# flight_controller_with_pcb_frame.net
KiCad netlist of a schematic drawn in EAGLE
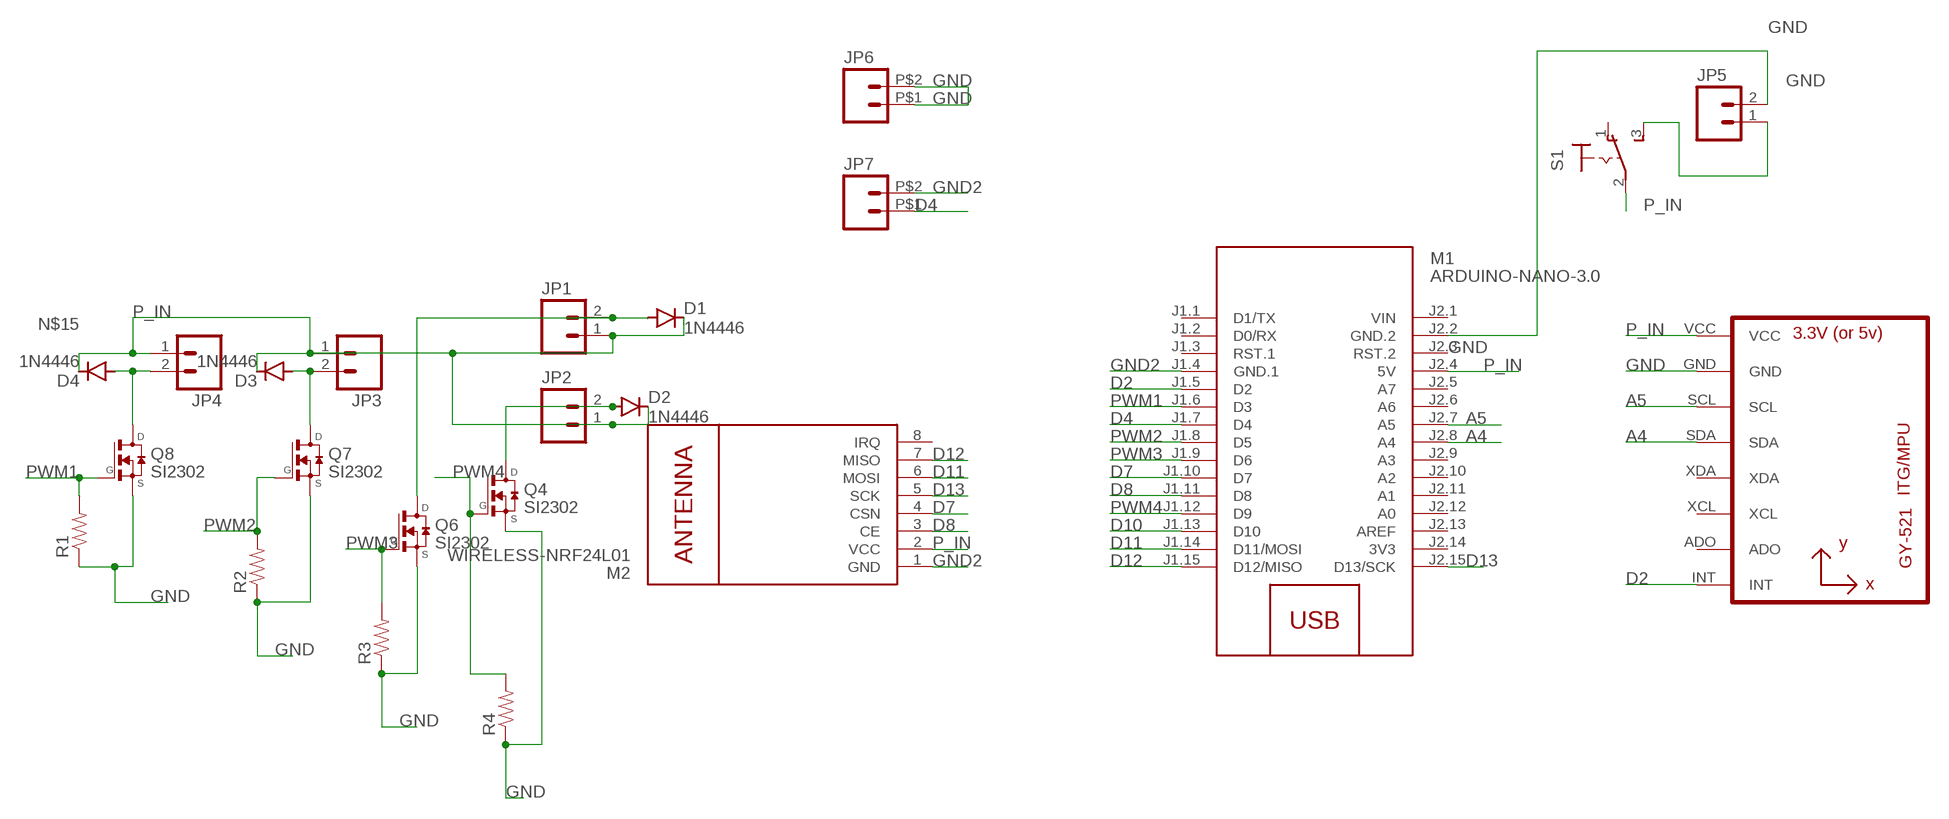
[diagram p0: schematic, sheet 1]

(export (version "E")
  (design (tool "Eeschema 10.0.6"))
  (components
    (comp (ref "D1")
      (value "1N4446")
      (footprint "eagle-import:DO35-10")
      (libsource (lib "eagle-import") (part "1N4446"))
    )
    (comp (ref "D2")
      (value "1N4446")
      (footprint "eagle-import:DO35-10")
      (libsource (lib "eagle-import") (part "1N4446"))
    )
    (comp (ref "D3")
      (value "1N4446")
      (footprint "eagle-import:DO35-10")
      (libsource (lib "eagle-import") (part "1N4446"))
    )
    (comp (ref "D4")
      (value "1N4446")
      (footprint "eagle-import:DO35-10")
      (libsource (lib "eagle-import") (part "1N4446"))
    )
    (comp (ref "JP1")
      (value "M021X02_NO_SILK")
      (footprint "eagle-import:1X02_NO_SILK")
      (libsource (lib "eagle-import") (part "M021X02_NO_SILK"))
    )
    (comp (ref "JP2")
      (value "M021X02_NO_SILK")
      (footprint "eagle-import:1X02_NO_SILK")
      (libsource (lib "eagle-import") (part "M021X02_NO_SILK"))
    )
    (comp (ref "JP3")
      (value "M021X02_NO_SILK")
      (footprint "eagle-import:1X02_NO_SILK")
      (libsource (lib "eagle-import") (part "M021X02_NO_SILK"))
    )
    (comp (ref "JP4")
      (value "M021X02_NO_SILK")
      (footprint "eagle-import:1X02_NO_SILK")
      (libsource (lib "eagle-import") (part "M021X02_NO_SILK"))
    )
    (comp (ref "JP5")
      (value "M02PTH")
      (footprint "eagle-import:1X02")
      (libsource (lib "eagle-import") (part "M02PTH"))
    )
    (comp (ref "JP6")
      (value "M02PTH2")
      (footprint "eagle-import:1X02_BIG")
      (libsource (lib "eagle-import") (part "M02PTH2"))
    )
    (comp (ref "JP7")
      (value "M02PTH2")
      (footprint "eagle-import:1X02_BIG")
      (libsource (lib "eagle-import") (part "M02PTH2"))
    )
    (comp (ref "M1")
      (value "ARDUINO-NANO-3.0")
      (footprint "eagle-import:ARDUINO-NANO-3.0")
      (libsource (lib "eagle-import") (part "ARDUINO-NANO-3.0"))
    )
    (comp (ref "M2")
      (value "WIRELESS-NRF24L01")
      (footprint "eagle-import:WIRELESS-NRF24L01")
      (libsource (lib "eagle-import") (part "WIRELESS-NRF24L01"))
    )
    (comp (ref "Q4")
      (value "SI2302")
      (footprint "eagle-import:SOT23")
      (libsource (lib "eagle-import") (part "SI2302"))
    )
    (comp (ref "Q6")
      (value "SI2302")
      (footprint "eagle-import:SOT23")
      (libsource (lib "eagle-import") (part "SI2302"))
    )
    (comp (ref "Q7")
      (value "SI2302")
      (footprint "eagle-import:SOT23")
      (libsource (lib "eagle-import") (part "SI2302"))
    )
    (comp (ref "Q8")
      (value "SI2302")
      (footprint "eagle-import:SOT23")
      (libsource (lib "eagle-import") (part "SI2302"))
    )
    (comp (ref "R1")
      (value "RESISTORAXIAL-0.3")
      (footprint "eagle-import:AXIAL-0.3")
      (libsource (lib "eagle-import") (part "RESISTORAXIAL-0.3"))
    )
    (comp (ref "R2")
      (value "RESISTORAXIAL-0.3")
      (footprint "eagle-import:AXIAL-0.3")
      (libsource (lib "eagle-import") (part "RESISTORAXIAL-0.3"))
    )
    (comp (ref "R3")
      (value "RESISTORAXIAL-0.3")
      (footprint "eagle-import:AXIAL-0.3")
      (libsource (lib "eagle-import") (part "RESISTORAXIAL-0.3"))
    )
    (comp (ref "R4")
      (value "RESISTORAXIAL-0.3")
      (footprint "eagle-import:AXIAL-0.3")
      (libsource (lib "eagle-import") (part "RESISTORAXIAL-0.3"))
    )
    (comp (ref "S1")
      (value "M9040P")
      (footprint "eagle-import:M9040P")
      (libsource (lib "eagle-import") (part "M9040P"))
    )
    (comp (ref "U1")
      (value "GY-521MPU6050")
      (footprint "eagle-import:GY-521")
      (libsource (lib "eagle-import") (part "GY-521MPU6050"))
    )
  )
  (nets
    (net (code "1") (name "/3V3") (class "Default")
      (node (ref "M1") (pin "J2.14") (pinfunction "3V3_J2.14") (pintype "power_in"))
    )
    (net (code "2") (name "/A4") (class "Default")
      (node (ref "M1") (pin "J2.8") (pinfunction "A4_J2.8") (pintype "bidirectional"))
      (node (ref "U1") (pin "SDA") (pinfunction "SDA_SDA") (pintype "bidirectional"))
    )
    (net (code "3") (name "/A5") (class "Default")
      (node (ref "M1") (pin "J2.7") (pinfunction "A5_J2.7") (pintype "bidirectional"))
      (node (ref "U1") (pin "SCL") (pinfunction "SCL_SCL") (pintype "bidirectional"))
    )
    (net (code "4") (name "/D2") (class "Default")
      (node (ref "M1") (pin "J1.5") (pinfunction "D2_J1.5") (pintype "bidirectional"))
      (node (ref "U1") (pin "INT") (pinfunction "INT_INT") (pintype "bidirectional"))
    )
    (net (code "5") (name "/D4") (class "Default")
      (node (ref "JP7") (pin "P$1") (pinfunction "1_P$1") (pintype "passive"))
      (node (ref "M1") (pin "J1.7") (pinfunction "D4_J1.7") (pintype "bidirectional"))
    )
    (net (code "6") (name "/D7") (class "Default")
      (node (ref "M1") (pin "J1.10") (pinfunction "D7_J1.10") (pintype "bidirectional"))
      (node (ref "M2") (pin "4") (pinfunction "CSN_4") (pintype "bidirectional"))
    )
    (net (code "7") (name "/D8") (class "Default")
      (node (ref "M1") (pin "J1.11") (pinfunction "D8_J1.11") (pintype "bidirectional"))
      (node (ref "M2") (pin "3") (pinfunction "CE_3") (pintype "bidirectional"))
    )
    (net (code "8") (name "/D10") (class "Default")
      (node (ref "M1") (pin "J1.13") (pinfunction "D10_J1.13") (pintype "bidirectional"))
    )
    (net (code "9") (name "/D11") (class "Default")
      (node (ref "M1") (pin "J1.14") (pinfunction "D11/MOSI_J1.14") (pintype "bidirectional"))
      (node (ref "M2") (pin "6") (pinfunction "MOSI_6") (pintype "bidirectional"))
    )
    (net (code "10") (name "/D12") (class "Default")
      (node (ref "M1") (pin "J1.15") (pinfunction "D12/MISO_J1.15") (pintype "bidirectional"))
      (node (ref "M2") (pin "7") (pinfunction "MISO_7") (pintype "bidirectional"))
    )
    (net (code "11") (name "/D13") (class "Default")
      (node (ref "M1") (pin "J2.15") (pinfunction "D13/SCK_J2.15") (pintype "bidirectional"))
      (node (ref "M2") (pin "5") (pinfunction "SCK_5") (pintype "bidirectional"))
    )
    (net (code "12") (name "/GND") (class "Default")
      (node (ref "JP5") (pin "2") (pinfunction "2_2") (pintype "passive"))
      (node (ref "JP6") (pin "P$1") (pinfunction "1_P$1") (pintype "passive"))
      (node (ref "JP6") (pin "P$2") (pinfunction "2_P$2") (pintype "passive"))
      (node (ref "M1") (pin "J2.2") (pinfunction "GND.2_J2.2") (pintype "power_in"))
      (node (ref "Q4") (pin "2") (pinfunction "S_2") (pintype "passive"))
      (node (ref "Q6") (pin "2") (pinfunction "S_2") (pintype "passive"))
      (node (ref "Q7") (pin "2") (pinfunction "S_2") (pintype "passive"))
      (node (ref "Q8") (pin "2") (pinfunction "S_2") (pintype "passive"))
      (node (ref "R1") (pin "P$1") (pinfunction "1_P$1") (pintype "passive"))
      (node (ref "R2") (pin "P$1") (pinfunction "1_P$1") (pintype "passive"))
      (node (ref "R3") (pin "P$1") (pinfunction "1_P$1") (pintype "passive"))
      (node (ref "R4") (pin "P$1") (pinfunction "1_P$1") (pintype "passive"))
      (node (ref "U1") (pin "GND") (pinfunction "GND_GND") (pintype "bidirectional"))
    )
    (net (code "13") (name "/GND2") (class "Default")
      (node (ref "JP7") (pin "P$2") (pinfunction "2_P$2") (pintype "passive"))
      (node (ref "M1") (pin "J1.4") (pinfunction "GND.1_J1.4") (pintype "power_in"))
      (node (ref "M2") (pin "1") (pinfunction "GND_1") (pintype "power_in"))
    )
    (net (code "14") (name "/N$15") (class "Default")
      (node (ref "D4") (pin "A") (pinfunction "A_A") (pintype "passive"))
      (node (ref "JP4") (pin "2") (pinfunction "2_2") (pintype "passive"))
      (node (ref "Q8") (pin "3") (pinfunction "D_3") (pintype "passive"))
    )
    (net (code "15") (name "/PWM1") (class "Default")
      (node (ref "M1") (pin "J1.6") (pinfunction "D3_J1.6") (pintype "bidirectional"))
      (node (ref "Q8") (pin "1") (pinfunction "G_1") (pintype "passive"))
      (node (ref "R1") (pin "P$2") (pinfunction "2_P$2") (pintype "passive"))
    )
    (net (code "16") (name "/PWM2") (class "Default")
      (node (ref "M1") (pin "J1.8") (pinfunction "D5_J1.8") (pintype "bidirectional"))
      (node (ref "Q7") (pin "1") (pinfunction "G_1") (pintype "passive"))
      (node (ref "R2") (pin "P$2") (pinfunction "2_P$2") (pintype "passive"))
    )
    (net (code "17") (name "/PWM3") (class "Default")
      (node (ref "M1") (pin "J1.9") (pinfunction "D6_J1.9") (pintype "bidirectional"))
      (node (ref "Q6") (pin "1") (pinfunction "G_1") (pintype "passive"))
      (node (ref "R3") (pin "P$2") (pinfunction "2_P$2") (pintype "passive"))
    )
    (net (code "18") (name "/PWM4") (class "Default")
      (node (ref "M1") (pin "J1.12") (pinfunction "D9_J1.12") (pintype "bidirectional"))
      (node (ref "Q4") (pin "1") (pinfunction "G_1") (pintype "passive"))
      (node (ref "R4") (pin "P$2") (pinfunction "2_P$2") (pintype "passive"))
    )
    (net (code "19") (name "/P_IN") (class "Default")
      (node (ref "D1") (pin "C") (pinfunction "C_C") (pintype "passive"))
      (node (ref "D2") (pin "C") (pinfunction "C_C") (pintype "passive"))
      (node (ref "D3") (pin "C") (pinfunction "C_C") (pintype "passive"))
      (node (ref "D4") (pin "C") (pinfunction "C_C") (pintype "passive"))
      (node (ref "JP1") (pin "1") (pinfunction "1_1") (pintype "passive"))
      (node (ref "JP2") (pin "1") (pinfunction "1_1") (pintype "passive"))
      (node (ref "JP3") (pin "1") (pinfunction "1_1") (pintype "passive"))
      (node (ref "JP4") (pin "1") (pinfunction "1_1") (pintype "passive"))
      (node (ref "M1") (pin "J2.4") (pinfunction "5V_J2.4") (pintype "power_in"))
      (node (ref "M2") (pin "2") (pinfunction "VCC_2") (pintype "power_in"))
      (node (ref "S1") (pin "2") (pinfunction "P_2") (pintype "passive"))
      (node (ref "U1") (pin "VCC") (pinfunction "VCC_VCC") (pintype "bidirectional"))
    )
    (net (code "20") (name "/VIN") (class "Default")
      (node (ref "M1") (pin "J2.1") (pinfunction "VIN_J2.1") (pintype "power_in"))
    )
    (net (code "21") (name "Net-(Q4-D)") (class "Default")
      (node (ref "D2") (pin "A") (pinfunction "A_A") (pintype "passive"))
      (node (ref "JP2") (pin "2") (pinfunction "2_2") (pintype "passive"))
      (node (ref "Q4") (pin "3") (pinfunction "D_3") (pintype "passive"))
    )
    (net (code "22") (name "Net-(Q6-D)") (class "Default")
      (node (ref "D1") (pin "A") (pinfunction "A_A") (pintype "passive"))
      (node (ref "JP1") (pin "2") (pinfunction "2_2") (pintype "passive"))
      (node (ref "Q6") (pin "3") (pinfunction "D_3") (pintype "passive"))
    )
    (net (code "23") (name "Net-(Q7-D)") (class "Default")
      (node (ref "D3") (pin "A") (pinfunction "A_A") (pintype "passive"))
      (node (ref "JP3") (pin "2") (pinfunction "2_2") (pintype "passive"))
      (node (ref "Q7") (pin "3") (pinfunction "D_3") (pintype "passive"))
    )
    (net (code "24") (name "Net-(S1-S)") (class "Default")
      (node (ref "JP5") (pin "1") (pinfunction "1_1") (pintype "passive"))
      (node (ref "S1") (pin "3") (pinfunction "S_3") (pintype "passive"))
    )
    (net (code "25") (name "unconnected-(M1-A0-PadJ2.12)") (class "Default")
      (node (ref "M1") (pin "J2.12") (pinfunction "A0_J2.12") (pintype "bidirectional"))
    )
    (net (code "26") (name "unconnected-(M1-A1-PadJ2.11)") (class "Default")
      (node (ref "M1") (pin "J2.11") (pinfunction "A1_J2.11") (pintype "bidirectional"))
    )
    (net (code "27") (name "unconnected-(M1-A2-PadJ2.10)") (class "Default")
      (node (ref "M1") (pin "J2.10") (pinfunction "A2_J2.10") (pintype "bidirectional"))
    )
    (net (code "28") (name "unconnected-(M1-A3-PadJ2.9)") (class "Default")
      (node (ref "M1") (pin "J2.9") (pinfunction "A3_J2.9") (pintype "bidirectional"))
    )
    (net (code "29") (name "unconnected-(M1-A6-PadJ2.6)") (class "Default")
      (node (ref "M1") (pin "J2.6") (pinfunction "A6_J2.6") (pintype "bidirectional"))
    )
    (net (code "30") (name "unconnected-(M1-A7-PadJ2.5)") (class "Default")
      (node (ref "M1") (pin "J2.5") (pinfunction "A7_J2.5") (pintype "bidirectional"))
    )
    (net (code "31") (name "unconnected-(M1-AREF-PadJ2.13)") (class "Default")
      (node (ref "M1") (pin "J2.13") (pinfunction "AREF_J2.13") (pintype "bidirectional"))
    )
    (net (code "32") (name "unconnected-(M1-D0{slash}RX-PadJ1.2)") (class "Default")
      (node (ref "M1") (pin "J1.2") (pinfunction "D0/RX_J1.2") (pintype "bidirectional"))
    )
    (net (code "33") (name "unconnected-(M1-D1{slash}TX-PadJ1.1)") (class "Default")
      (node (ref "M1") (pin "J1.1") (pinfunction "D1/TX_J1.1") (pintype "bidirectional"))
    )
    (net (code "34") (name "unconnected-(M1-RST.1-PadJ1.3)") (class "Default")
      (node (ref "M1") (pin "J1.3") (pinfunction "RST.1_J1.3") (pintype "bidirectional"))
    )
    (net (code "35") (name "unconnected-(M1-RST.2-PadJ2.3)") (class "Default")
      (node (ref "M1") (pin "J2.3") (pinfunction "RST.2_J2.3") (pintype "bidirectional"))
    )
    (net (code "36") (name "unconnected-(M2-IRQ-Pad8)") (class "Default")
      (node (ref "M2") (pin "8") (pinfunction "IRQ_8") (pintype "bidirectional"))
    )
    (net (code "37") (name "unconnected-(S1-O-Pad1)") (class "Default")
      (node (ref "S1") (pin "1") (pinfunction "O_1") (pintype "passive"))
    )
    (net (code "38") (name "unconnected-(U1-PadADO)") (class "Default")
      (node (ref "U1") (pin "ADO") (pinfunction "ADO_ADO") (pintype "bidirectional"))
    )
    (net (code "39") (name "unconnected-(U1-PadXCL)") (class "Default")
      (node (ref "U1") (pin "XCL") (pinfunction "XCL_XCL") (pintype "bidirectional"))
    )
    (net (code "40") (name "unconnected-(U1-PadXDA)") (class "Default")
      (node (ref "U1") (pin "XDA") (pinfunction "XDA_XDA") (pintype "bidirectional"))
    )
  )
)
